# Power.net
KiCad netlist of a schematic drawn in Altium Designer
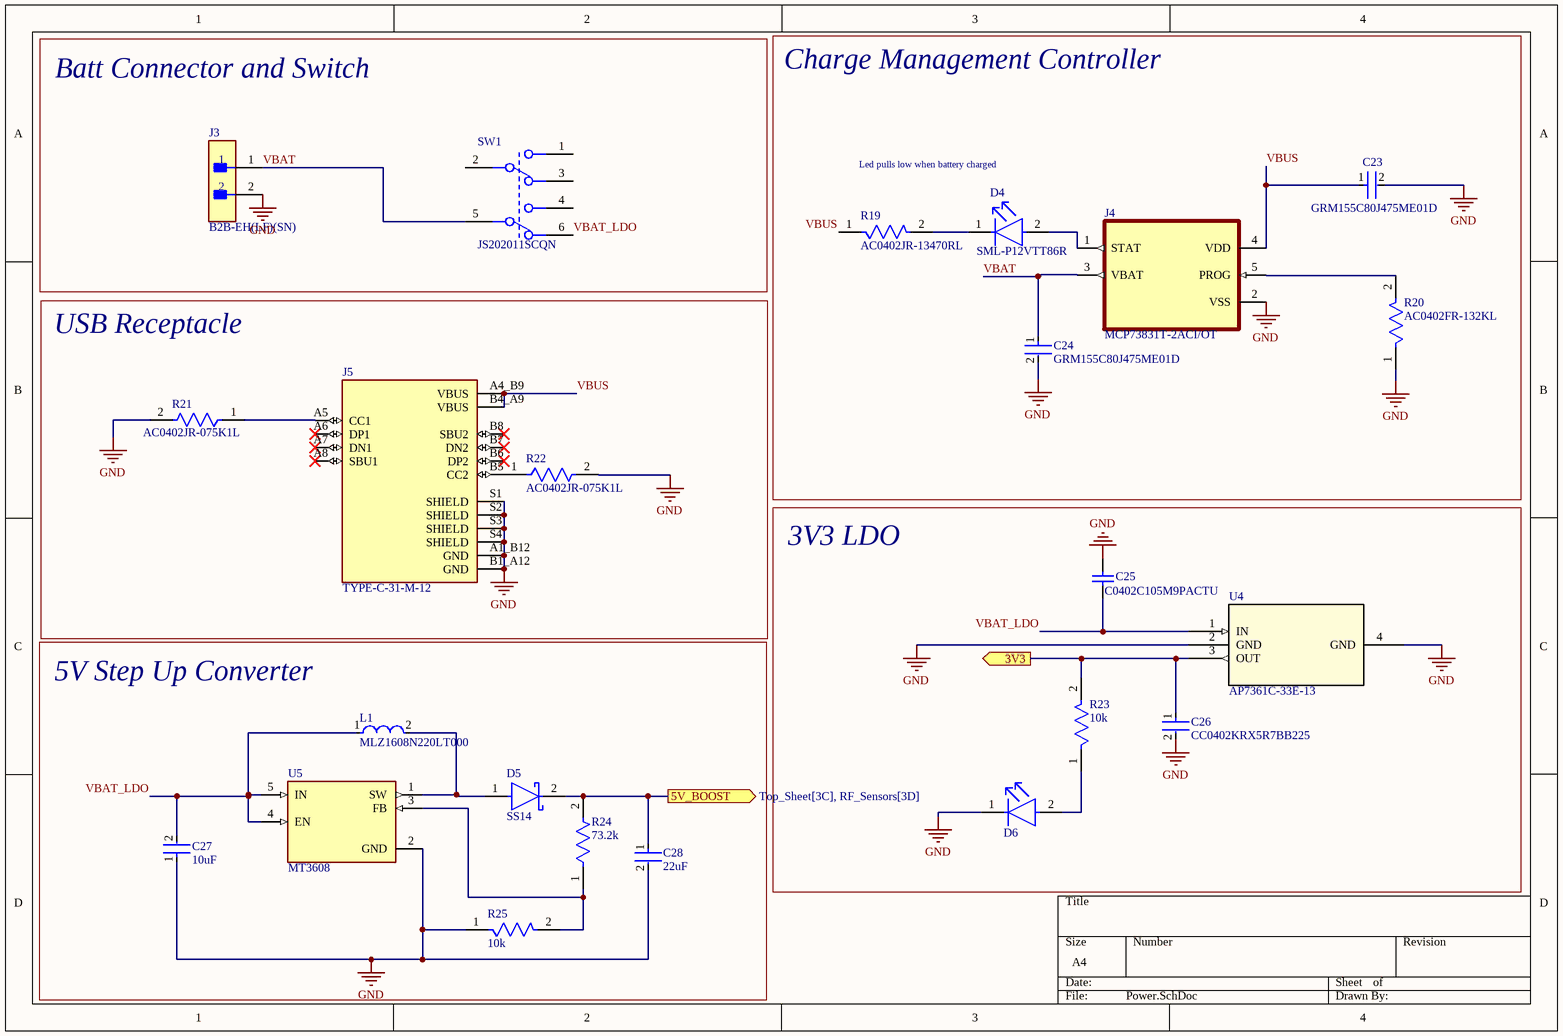
[diagram p0: Power.SchDoc]

(export (version "E")
  (design (tool "Eeschema 10.0.6"))
  (components
    (comp (ref "C23")
      (value "GRM155C80J475ME01D")
      (footprint "FP-GRM155-0_2-MFG")
      (libsource (lib "Altium Content Vault") (part "b4654b650e69147ec39a6b967a45e02"))
    )
    (comp (ref "C24")
      (value "GRM155C80J475ME01D")
      (footprint "FP-GRM155-0_2-MFG")
      (libsource (lib "Altium Content Vault") (part "b4654b650e69147ec39a6b967a45e02"))
    )
    (comp (ref "C25")
      (value "C0402C105M9PACTU")
      (footprint "CAPC1005X60X30ML05T10")
      (fields (field (name "MANUFACTURER") "Kemet"))
      (libsource (lib "Altium Content Vault") (part "CAP"))
    )
    (comp (ref "C26")
      (value "CC0402KRX5R7BB225")
      (footprint "FP-CC0402-CC-MFG")
      (description "CAP CER 2.2UF 16V X5R 0402")
      (fields (field (name "TOLERANCE") "10%"))
      (libsource (lib "Altium Content Vault") (part "b4654b650e69147ec39a6b967a45e02"))
    )
    (comp (ref "C27")
      (value "10uF")
      (footprint "FP-C0402C106M9PACTU-MFG")
      (description "CAP CER 10UF 6.3V X5R 0402")
      (fields (field (name "TOLERANCE") "20%"))
      (libsource (lib "Altium Content Vault") (part "b4654b650e69147ec39a6b967a45e02"))
    )
    (comp (ref "C28")
      (value "22uF")
      (footprint "FP-GRM158-0_2-MFG")
      (description "Chip Multilayer Ceramic Capacitors for General Purpose, 0402, 22uF, X5R, 15%, 20%, 10V")
      (libsource (lib "Altium Content Vault") (part "b4654b650e69147ec39a6b967a45e02"))
    )
    (comp (ref "D4")
      (value "SML-P12VTT86R")
      (footprint "FP-SML-P1-MFG")
      (description "LED RED CLEAR 0402 SMD")
      (fields
        (field (name "OCTOPART") "https://octopart.com/sml-p12vtt86r-rohm-34112315")
        (field (name "MANUFACTURER") "Rohm")
      )
      (libsource (lib "Altium Content Vault") (part "8706943c75ba83719d021d2fdc84c58"))
    )
    (comp (ref "D5")
      (value "SS14")
      (footprint "FP-403AE-MFG")
      (description "DIODE SCHOTTKY 40V 1A SMA")
      (fields
        (field (name "MANUFACTURER") "ON Semiconductor")
        (field (name "OCTOPART") "https://octopart.com/ss14-on+semiconductor-29205033")
      )
      (libsource (lib "Altium Content Vault") (part "360ad2f4ac25a952324d13796385471"))
    )
    (comp (ref "D6")
      (value "SML-P12VTT86R")
      (footprint "FP-SML-P1-MFG")
      (description "LED RED CLEAR 0402 SMD")
      (fields
        (field (name "OCTOPART") "https://octopart.com/sml-p12vtt86r-rohm-34112315")
        (field (name "MANUFACTURER") "Rohm")
      )
      (libsource (lib "Altium Content Vault") (part "8706943c75ba83719d021d2fdc84c58"))
    )
    (comp (ref "J3")
      (value "B2B-EH(LF)(SN)")
      (footprint "FP-B2B-EH_LF_SN-MFG")
      (description "Connector Header, EH Series, 2 Position, 2.5mm, Through Hole, Press-Fit, Solder, Natural")
      (libsource (lib "Altium Content Vault") (part "3bc925449376181038e59eaffc5286c"))
    )
    (comp (ref "J4")
      (value "MCP73831T-2ACI/OT")
      (footprint "SOT95P280X145-5N")
      (description "Charger IC Lithium Ion/Polymer SOT-23-5")
      (fields (field (name "MF") "Microchip"))
      (libsource (lib "MCP73831T-2ACI_OT") (part "MCP73831T-2ACI/OT"))
    )
    (comp (ref "J5")
      (value "TYPE-C-31-M-12")
      (footprint "HRO_TYPE-C-31-M-12")
      (description "USB Connectors 24 Receptacle 1 8.94*7.3mm RoHS")
      (fields (field (name "MF") "HRO Electronics Co., Ltd."))
      (libsource (lib "TYPE-C-31-M-12") (part "TYPE-C-31-M-12"))
    )
    (comp (ref "L1")
      (value "MLZ1608N220LT000")
      (footprint "FP-MLZ1608-IPC_A")
      (description "Shielded Multilayer Inductor 22uH ±20% 190mA 2145mΩ SMD 0603")
      (fields (field (name "TOLERANCE") "20%"))
      (libsource (lib "Altium Content Vault") (part "725321dda6339637d4d059423bc1c3c"))
    )
    (comp (ref "R19")
      (value "AC0402JR-13470RL")
      (footprint "FP-AC0402-MFG")
      (description "RES 470Ω ±5% 0.063W 0402")
      (libsource (lib "Altium Content Vault") (part "1029c3af85768c4190bb7ad29bc67b5"))
    )
    (comp (ref "R20")
      (value "AC0402FR-132KL")
      (footprint "FP-AC0402-IPC_A")
      (description "RES 2kΩ ±1% 0.063W 0402")
      (libsource (lib "Altium Content Vault") (part "1029c3af85768c4190bb7ad29bc67b5"))
    )
    (comp (ref "R21")
      (value "AC0402JR-075K1L")
      (footprint "FP-AC0402-IPC_C")
      (description "RES 5.1kΩ ±5% 0.063W 0402")
      (fields (field (name "TOLERANCE") "5%"))
      (libsource (lib "Altium Content Vault") (part "1029c3af85768c4190bb7ad29bc67b5"))
    )
    (comp (ref "R22")
      (value "AC0402JR-075K1L")
      (footprint "FP-AC0402-IPC_C")
      (description "RES 5.1kΩ ±5% 0.063W 0402")
      (fields (field (name "TOLERANCE") "5%"))
      (libsource (lib "Altium Content Vault") (part "1029c3af85768c4190bb7ad29bc67b5"))
    )
    (comp (ref "R23")
      (value "10k")
      (footprint "FP-AC0402-MFG")
      (description "RES 470Ω ±5% 0.063W 0402")
      (libsource (lib "Altium Content Vault") (part "1029c3af85768c4190bb7ad29bc67b5"))
    )
    (comp (ref "R24")
      (value "73.2k")
      (footprint "FP-AF0402-IPC_C")
      (description "Anti-Sulfurated Chip Resistors Automotive Grade 73.2kΩ 1% 100ppm/°C 0402")
      (fields (field (name "TOLERANCE") "1%"))
      (libsource (lib "Altium Content Vault") (part "1029c3af85768c4190bb7ad29bc67b5"))
    )
    (comp (ref "R25")
      (value "10k")
      (footprint "FP-AC0402-MFG")
      (description "RES 470Ω ±5% 0.063W 0402")
      (libsource (lib "Altium Content Vault") (part "1029c3af85768c4190bb7ad29bc67b5"))
    )
    (comp (ref "SW1")
      (value "JS202011SCQN")
      (footprint "FP-JS202011SCQN-MFG")
      (description "SWITCH SLIDE DPDT 300MA 6V")
      (libsource (lib "Altium Content Vault") (part "ac99ea1af431c19115f5225061c5c88"))
    )
    (comp (ref "U4")
      (value "AP7361C-33E-13")
      (footprint "SOT223_DIO")
      (description "Description")
      (fields (field (name "COPYRIGHT") "Copyright (C) 2025 Ultra Librarian. All rights reserved."))
      (libsource (lib "AP7361C-33E-13") (part "AP7361C-33E-13"))
    )
    (comp (ref "U5")
      (value "MT3608")
      (footprint "SOT95P280X145-6N")
      (description "High Efficiency 1.2MHz2A Step Up Converter")
      (fields (field (name "MF") "Aerosemi Technology Co., Ltd"))
      (libsource (lib "MT3608") (part "MT3608"))
    )
  )
  (nets
    (net (code "1") (name "/3V3") (class "Default")
      (node (ref "C26") (pin "1") (pinfunction "1_1") (pintype "passive"))
      (node (ref "R23") (pin "2") (pinfunction "2_2") (pintype "passive"))
      (node (ref "U4") (pin "3") (pinfunction "OUT_3") (pintype "output"))
    )
    (net (code "2") (name "/5V_BOOST") (class "Default")
      (node (ref "C28") (pin "1") (pinfunction "1_1") (pintype "passive"))
      (node (ref "D5") (pin "2") (pinfunction "C_2") (pintype "passive"))
      (node (ref "R24") (pin "2") (pinfunction "2_2") (pintype "passive"))
    )
    (net (code "3") (name "/VBAT") (class "Default")
      (node (ref "C24") (pin "1") (pinfunction "1_1") (pintype "passive"))
      (node (ref "J3") (pin "1") (pinfunction "1_1") (pintype "passive"))
      (node (ref "J4") (pin "3") (pinfunction "VBAT_3") (pintype "output"))
      (node (ref "SW1") (pin "5") (pinfunction "5_5") (pintype "passive"))
    )
    (net (code "4") (name "/VBAT_LDO") (class "Default")
      (node (ref "C25") (pin "1") (pinfunction "1_1") (pintype "passive"))
      (node (ref "C27") (pin "2") (pinfunction "2_2") (pintype "passive"))
      (node (ref "L1") (pin "1") (pinfunction "1_1") (pintype "passive"))
      (node (ref "SW1") (pin "6") (pinfunction "6_6") (pintype "passive"))
      (node (ref "U4") (pin "1") (pinfunction "IN_1") (pintype "input"))
      (node (ref "U5") (pin "4") (pinfunction "EN_4") (pintype "input"))
      (node (ref "U5") (pin "5") (pinfunction "IN_5") (pintype "input"))
    )
    (net (code "5") (name "/VBUS") (class "Default")
      (node (ref "C23") (pin "1") (pinfunction "1_1") (pintype "passive"))
      (node (ref "J4") (pin "4") (pinfunction "VDD_4") (pintype "power_in"))
      (node (ref "J5") (pin "A4_B9") (pinfunction "VBUS_A4_B9") (pintype "power_in"))
      (node (ref "J5") (pin "B4_A9") (pinfunction "VBUS_B4_A9") (pintype "power_in"))
      (node (ref "R19") (pin "1") (pinfunction "1_1") (pintype "passive"))
    )
    (net (code "6") (name "GND") (class "Default")
      (node (ref "C23") (pin "2") (pinfunction "2_2") (pintype "passive"))
      (node (ref "C24") (pin "2") (pinfunction "2_2") (pintype "passive"))
      (node (ref "C25") (pin "2") (pinfunction "2_2") (pintype "passive"))
      (node (ref "C26") (pin "2") (pinfunction "2_2") (pintype "passive"))
      (node (ref "C27") (pin "1") (pinfunction "1_1") (pintype "passive"))
      (node (ref "C28") (pin "2") (pinfunction "2_2") (pintype "passive"))
      (node (ref "D6") (pin "1") (pinfunction "C_1") (pintype "passive"))
      (node (ref "J3") (pin "2") (pinfunction "2_2") (pintype "passive"))
      (node (ref "J4") (pin "2") (pinfunction "VSS_2") (pintype "power_in"))
      (node (ref "J5") (pin "A1_B12") (pinfunction "GND_A1_B12") (pintype "power_in"))
      (node (ref "J5") (pin "B1_A12") (pinfunction "GND_B1_A12") (pintype "power_in"))
      (node (ref "J5") (pin "S1") (pinfunction "SHIELD_S1") (pintype "passive"))
      (node (ref "J5") (pin "S2") (pinfunction "SHIELD_S2") (pintype "passive"))
      (node (ref "J5") (pin "S3") (pinfunction "SHIELD_S3") (pintype "passive"))
      (node (ref "J5") (pin "S4") (pinfunction "SHIELD_S4") (pintype "passive"))
      (node (ref "R20") (pin "1") (pinfunction "1_1") (pintype "passive"))
      (node (ref "R21") (pin "2") (pinfunction "2_2") (pintype "passive"))
      (node (ref "R22") (pin "2") (pinfunction "2_2") (pintype "passive"))
      (node (ref "R25") (pin "1") (pinfunction "1_1") (pintype "passive"))
      (node (ref "U4") (pin "2") (pinfunction "GND_2") (pintype "power_in"))
      (node (ref "U4") (pin "4") (pinfunction "GND_4") (pintype "power_in"))
      (node (ref "U5") (pin "2") (pinfunction "GND_2") (pintype "power_in"))
    )
    (net (code "7") (name "Net-(D4-A)") (class "Default")
      (node (ref "D4") (pin "2") (pinfunction "A_2") (pintype "passive"))
      (node (ref "J4") (pin "1") (pinfunction "STAT_1") (pintype "output"))
    )
    (net (code "8") (name "Net-(D4-C)") (class "Default")
      (node (ref "D4") (pin "1") (pinfunction "C_1") (pintype "passive"))
      (node (ref "R19") (pin "2") (pinfunction "2_2") (pintype "passive"))
    )
    (net (code "9") (name "Net-(D5-A)") (class "Default")
      (node (ref "D5") (pin "1") (pinfunction "A_1") (pintype "passive"))
      (node (ref "L1") (pin "2") (pinfunction "2_2") (pintype "passive"))
      (node (ref "U5") (pin "1") (pinfunction "SW_1") (pintype "output"))
    )
    (net (code "10") (name "Net-(D6-A)") (class "Default")
      (node (ref "D6") (pin "2") (pinfunction "A_2") (pintype "passive"))
      (node (ref "R23") (pin "1") (pinfunction "1_1") (pintype "passive"))
    )
    (net (code "11") (name "Net-(J4-PROG)") (class "Default")
      (node (ref "J4") (pin "5") (pinfunction "PROG_5") (pintype "input"))
      (node (ref "R20") (pin "2") (pinfunction "2_2") (pintype "passive"))
    )
    (net (code "12") (name "Net-(J5-CC1)") (class "Default")
      (node (ref "J5") (pin "A5") (pinfunction "CC1_A5") (pintype "bidirectional"))
      (node (ref "R21") (pin "1") (pinfunction "1_1") (pintype "passive"))
    )
    (net (code "13") (name "Net-(J5-CC2)") (class "Default")
      (node (ref "J5") (pin "B5") (pinfunction "CC2_B5") (pintype "bidirectional"))
      (node (ref "R22") (pin "1") (pinfunction "1_1") (pintype "passive"))
    )
    (net (code "14") (name "Net-(U5-FB)") (class "Default")
      (node (ref "R24") (pin "1") (pinfunction "1_1") (pintype "passive"))
      (node (ref "R25") (pin "2") (pinfunction "2_2") (pintype "passive"))
      (node (ref "U5") (pin "3") (pinfunction "FB_3") (pintype "input"))
    )
    (net (code "15") (name "unconnected-(J5-DN1-PadA7)") (class "Default")
      (node (ref "J5") (pin "A7") (pinfunction "DN1_A7") (pintype "bidirectional+no_connect"))
    )
    (net (code "16") (name "unconnected-(J5-DN2-PadB7)") (class "Default")
      (node (ref "J5") (pin "B7") (pinfunction "DN2_B7") (pintype "bidirectional+no_connect"))
    )
    (net (code "17") (name "unconnected-(J5-DP1-PadA6)") (class "Default")
      (node (ref "J5") (pin "A6") (pinfunction "DP1_A6") (pintype "bidirectional+no_connect"))
    )
    (net (code "18") (name "unconnected-(J5-DP2-PadB6)") (class "Default")
      (node (ref "J5") (pin "B6") (pinfunction "DP2_B6") (pintype "bidirectional+no_connect"))
    )
    (net (code "19") (name "unconnected-(J5-SBU1-PadA8)") (class "Default")
      (node (ref "J5") (pin "A8") (pinfunction "SBU1_A8") (pintype "bidirectional+no_connect"))
    )
    (net (code "20") (name "unconnected-(J5-SBU2-PadB8)") (class "Default")
      (node (ref "J5") (pin "B8") (pinfunction "SBU2_B8") (pintype "bidirectional+no_connect"))
    )
    (net (code "21") (name "unconnected-(SW1-Pad1)") (class "Default")
      (node (ref "SW1") (pin "1") (pinfunction "1_1") (pintype "passive"))
    )
    (net (code "22") (name "unconnected-(SW1-Pad2)") (class "Default")
      (node (ref "SW1") (pin "2") (pinfunction "2_2") (pintype "passive"))
    )
    (net (code "23") (name "unconnected-(SW1-Pad3)") (class "Default")
      (node (ref "SW1") (pin "3") (pinfunction "3_3") (pintype "passive"))
    )
    (net (code "24") (name "unconnected-(SW1-Pad4)") (class "Default")
      (node (ref "SW1") (pin "4") (pinfunction "4_4") (pintype "passive"))
    )
  )
)
